# Adafruit_SCD-41.net
KiCad netlist of a schematic drawn in EAGLE
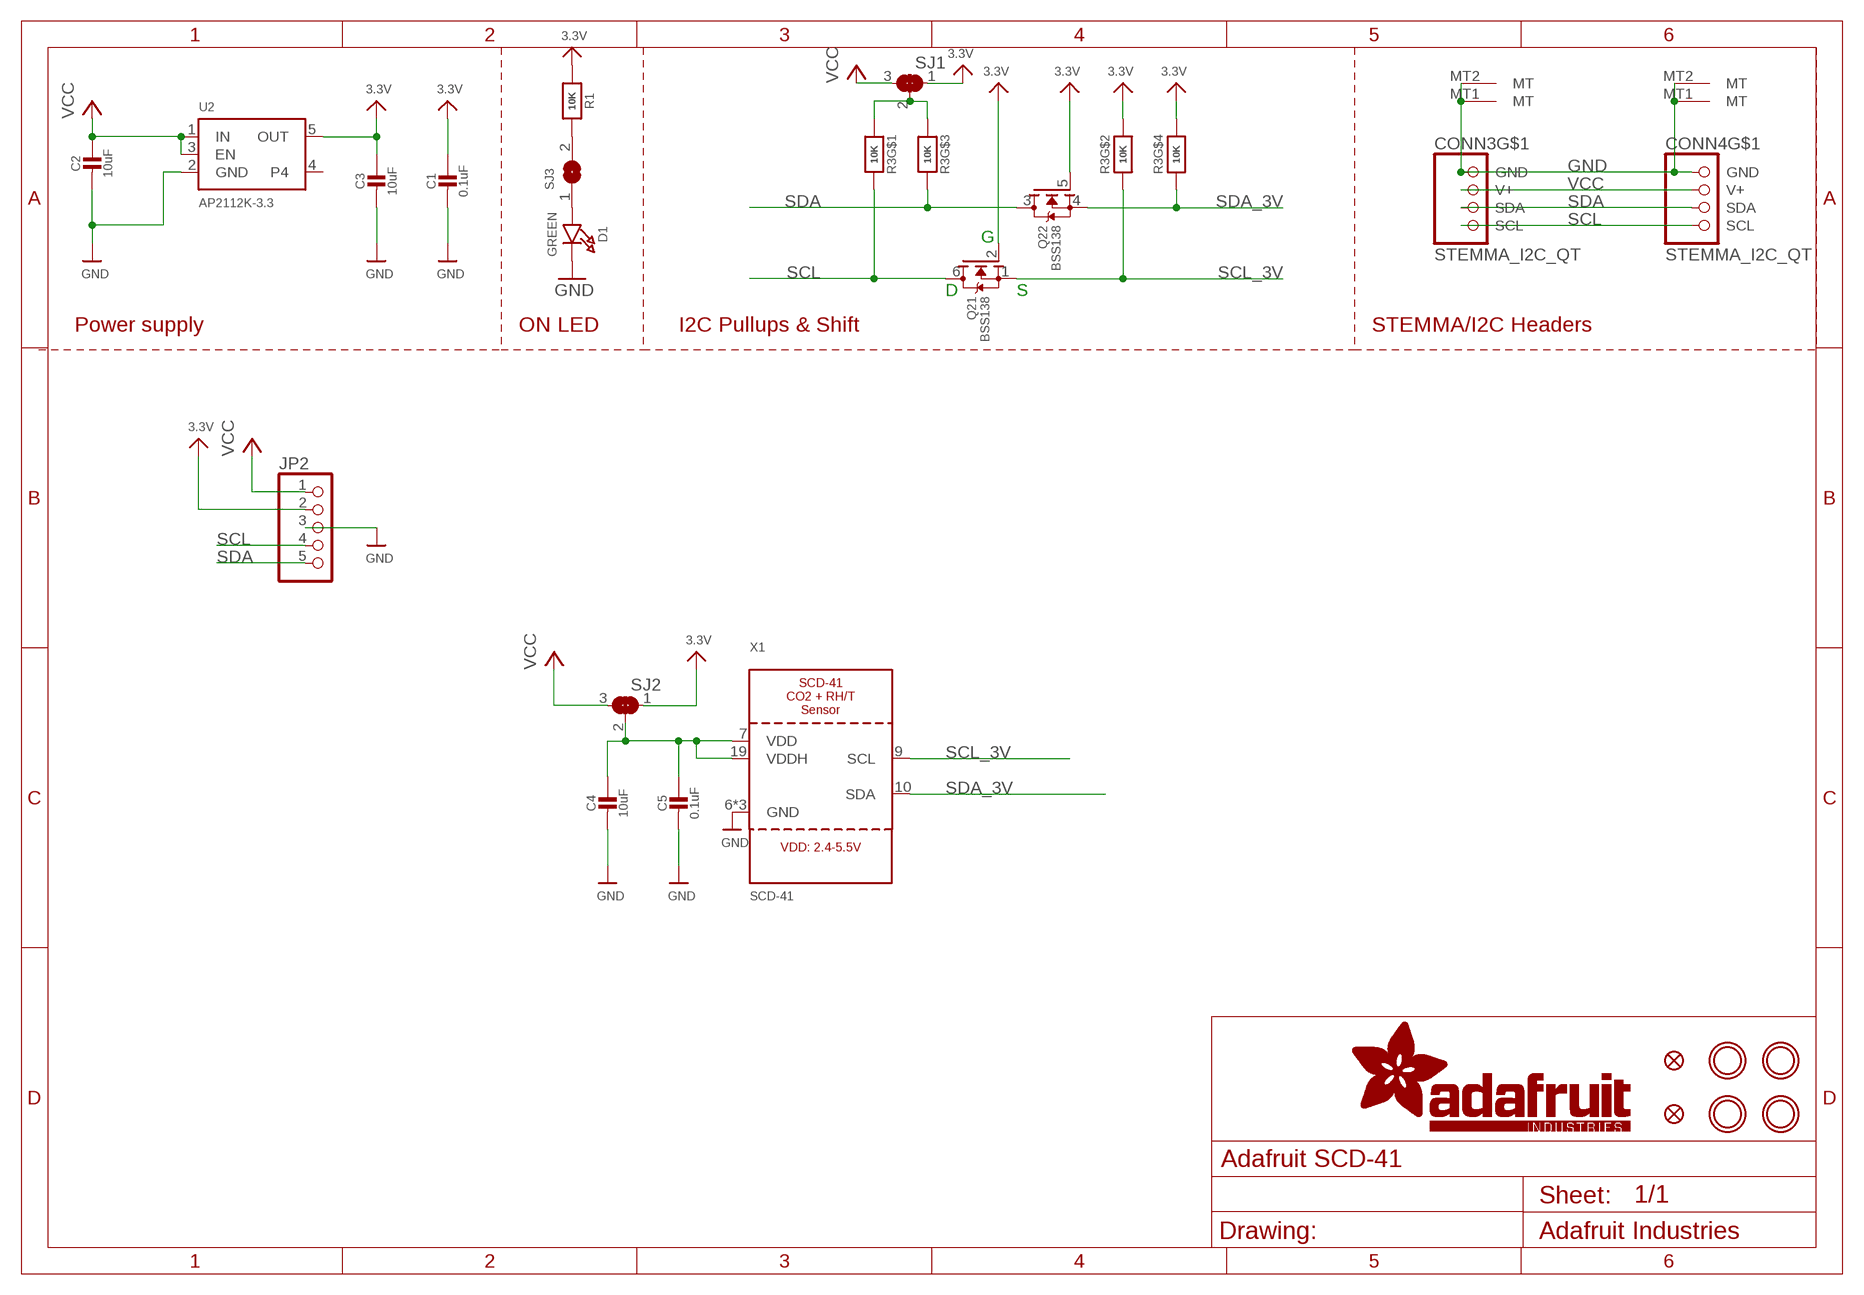
[diagram p0: schematic, sheet 1]

(export (version "E")
  (design (tool "Eeschema 10.0.6"))
  (components
    (comp (ref "C1")
      (value "0.1uF")
      (footprint "eagle-import:0603-NO")
      (libsource (lib "eagle-import") (part "CAP_CERAMIC0603_NO"))
    )
    (comp (ref "C2")
      (value "10uF")
      (footprint "eagle-import:0805-NO")
      (libsource (lib "eagle-import") (part "CAP_CERAMIC0805-NOOUTLINE"))
    )
    (comp (ref "C3")
      (value "10uF")
      (footprint "eagle-import:0805-NO")
      (libsource (lib "eagle-import") (part "CAP_CERAMIC0805-NOOUTLINE"))
    )
    (comp (ref "C4")
      (value "10uF")
      (footprint "eagle-import:0805-NO")
      (libsource (lib "eagle-import") (part "CAP_CERAMIC0805-NOOUTLINE"))
    )
    (comp (ref "C5")
      (value "0.1uF")
      (footprint "eagle-import:0603-NO")
      (libsource (lib "eagle-import") (part "CAP_CERAMIC0603_NO"))
    )
    (comp (ref "CONN3")
      (value "STEMMA_I2C_QT")
      (footprint "eagle-import:JST_SH4")
      (libsource (lib "eagle-import") (part "STEMMA_I2C_QT"))
    )
    (comp (ref "CONN4")
      (value "STEMMA_I2C_QT")
      (footprint "eagle-import:JST_SH4")
      (libsource (lib "eagle-import") (part "STEMMA_I2C_QT"))
    )
    (comp (ref "D1")
      (value "GREEN")
      (footprint "eagle-import:CHIPLED_0603_NOOUTLINE")
      (libsource (lib "eagle-import") (part "LED0603_NOOUTLINE"))
    )
    (comp (ref "FID3")
      (value "FIDUCIAL_1MM")
      (footprint "eagle-import:FIDUCIAL_1MM")
      (libsource (lib "eagle-import") (part "FIDUCIAL_1MM"))
    )
    (comp (ref "FID4")
      (value "FIDUCIAL_1MM")
      (footprint "eagle-import:FIDUCIAL_1MM")
      (libsource (lib "eagle-import") (part "FIDUCIAL_1MM"))
    )
    (comp (ref "JP2")
      (value "HEADER-1X576MIL")
      (footprint "eagle-import:1X05_ROUND_76")
      (libsource (lib "eagle-import") (part "HEADER-1X576MIL"))
    )
    (comp (ref "Q2")
      (value "BSS138")
      (footprint "eagle-import:SOT363")
      (libsource (lib "eagle-import") (part "MOSFET-N_DUAL"))
    )
    (comp (ref "R1")
      (value "10K")
      (footprint "eagle-import:0603-NO")
      (libsource (lib "eagle-import") (part "RESISTOR_0603_NOOUT"))
    )
    (comp (ref "R3")
      (value "10K")
      (footprint "eagle-import:RESPACK_4X0603")
      (libsource (lib "eagle-import") (part "RESISTOR_4PACK"))
    )
    (comp (ref "SJ1")
      (value "SOLDERJUMPER_2WAY")
      (footprint "eagle-import:SOLDERJUMPER_2WAY_OPEN_NOPASTE")
      (libsource (lib "eagle-import") (part "SOLDERJUMPER_2WAY"))
    )
    (comp (ref "SJ2")
      (value "SOLDERJUMPER_2WAY")
      (footprint "eagle-import:SOLDERJUMPER_2WAY_OPEN_NOPASTE")
      (libsource (lib "eagle-import") (part "SOLDERJUMPER_2WAY"))
    )
    (comp (ref "SJ3")
      (value "SOLDERJUMPERCLOSED")
      (footprint "eagle-import:SOLDERJUMPER_CLOSEDWIRE")
      (libsource (lib "eagle-import") (part "SOLDERJUMPERCLOSED"))
    )
    (comp (ref "U$1")
      (value "MOUNTINGHOLE3.0THIN")
      (footprint "eagle-import:MOUNTINGHOLE_3.0_PLATEDTHIN")
      (libsource (lib "eagle-import") (part "MOUNTINGHOLE3.0THIN"))
    )
    (comp (ref "U$17")
      (value "MOUNTINGHOLE3.0THIN")
      (footprint "eagle-import:MOUNTINGHOLE_3.0_PLATEDTHIN")
      (libsource (lib "eagle-import") (part "MOUNTINGHOLE3.0THIN"))
    )
    (comp (ref "U$19")
      (value "MOUNTINGHOLE3.0THIN")
      (footprint "eagle-import:MOUNTINGHOLE_3.0_PLATEDTHIN")
      (libsource (lib "eagle-import") (part "MOUNTINGHOLE3.0THIN"))
    )
    (comp (ref "U$21")
      (value "MOUNTINGHOLE3.0THIN")
      (footprint "eagle-import:MOUNTINGHOLE_3.0_PLATEDTHIN")
      (libsource (lib "eagle-import") (part "MOUNTINGHOLE3.0THIN"))
    )
    (comp (ref "U2")
      (value "AP2112K-3.3")
      (footprint "eagle-import:SOT23-5")
      (libsource (lib "eagle-import") (part "VREG_SOT23-5"))
    )
    (comp (ref "X1")
      (value "SCD-41")
      (footprint "eagle-import:SCD41")
      (libsource (lib "eagle-import") (part "SCD-41"))
    )
  )
  (nets
    (net (code "1") (name "/SCL") (class "Default")
      (node (ref "CONN3") (pin "4") (pinfunction "SCL_4") (pintype "passive"))
      (node (ref "CONN4") (pin "4") (pinfunction "SCL_4") (pintype "passive"))
      (node (ref "JP2") (pin "4") (pinfunction "4_4") (pintype "passive"))
      (node (ref "Q2") (pin "6") (pinfunction "D_6") (pintype "bidirectional"))
      (node (ref "R3") (pin "8") (pinfunction "2_8") (pintype "passive"))
    )
    (net (code "2") (name "/SCL_3V") (class "Default")
      (node (ref "Q2") (pin "1") (pinfunction "S_1") (pintype "bidirectional"))
      (node (ref "R3") (pin "7") (pinfunction "2_7") (pintype "passive"))
      (node (ref "X1") (pin "9") (pinfunction "SCL_9") (pintype "input"))
    )
    (net (code "3") (name "/SDA") (class "Default")
      (node (ref "CONN3") (pin "3") (pinfunction "SDA_3") (pintype "passive"))
      (node (ref "CONN4") (pin "3") (pinfunction "SDA_3") (pintype "passive"))
      (node (ref "JP2") (pin "5") (pinfunction "5_5") (pintype "passive"))
      (node (ref "Q2") (pin "3") (pinfunction "D_3") (pintype "bidirectional"))
      (node (ref "R3") (pin "6") (pinfunction "2_6") (pintype "passive"))
    )
    (net (code "4") (name "/SDA_3V") (class "Default")
      (node (ref "Q2") (pin "4") (pinfunction "S_4") (pintype "bidirectional"))
      (node (ref "R3") (pin "5") (pinfunction "2_5") (pintype "passive"))
      (node (ref "X1") (pin "10") (pinfunction "SDA_10") (pintype "bidirectional"))
    )
    (net (code "5") (name "3.3V") (class "Default")
      (node (ref "C1") (pin "1") (pinfunction "1_1") (pintype "passive"))
      (node (ref "C3") (pin "1") (pinfunction "1_1") (pintype "passive"))
      (node (ref "JP2") (pin "2") (pinfunction "2_2") (pintype "passive"))
      (node (ref "Q2") (pin "2") (pinfunction "G_2") (pintype "bidirectional"))
      (node (ref "Q2") (pin "5") (pinfunction "G_5") (pintype "bidirectional"))
      (node (ref "R1") (pin "1") (pinfunction "1_1") (pintype "passive"))
      (node (ref "R3") (pin "2") (pinfunction "1_2") (pintype "passive"))
      (node (ref "R3") (pin "4") (pinfunction "1_4") (pintype "passive"))
      (node (ref "SJ1") (pin "1") (pinfunction "1_1") (pintype "passive"))
      (node (ref "SJ2") (pin "1") (pinfunction "1_1") (pintype "passive"))
      (node (ref "U2") (pin "5") (pinfunction "OUT_5") (pintype "power_in"))
    )
    (net (code "6") (name "GND") (class "Default")
      (node (ref "C1") (pin "2") (pinfunction "2_2") (pintype "passive"))
      (node (ref "C2") (pin "2") (pinfunction "2_2") (pintype "passive"))
      (node (ref "C3") (pin "2") (pinfunction "2_2") (pintype "passive"))
      (node (ref "C4") (pin "2") (pinfunction "2_2") (pintype "passive"))
      (node (ref "C5") (pin "2") (pinfunction "2_2") (pintype "passive"))
      (node (ref "CONN3") (pin "1") (pinfunction "GND_1") (pintype "passive"))
      (node (ref "CONN3") (pin "MT1") (pinfunction "MT_MT1") (pintype "bidirectional"))
      (node (ref "CONN3") (pin "MT2") (pinfunction "MT_MT2") (pintype "bidirectional"))
      (node (ref "CONN4") (pin "1") (pinfunction "GND_1") (pintype "passive"))
      (node (ref "CONN4") (pin "MT1") (pinfunction "MT_MT1") (pintype "bidirectional"))
      (node (ref "CONN4") (pin "MT2") (pinfunction "MT_MT2") (pintype "bidirectional"))
      (node (ref "D1") (pin "C") (pinfunction "C_C") (pintype "passive"))
      (node (ref "JP2") (pin "3") (pinfunction "3_3") (pintype "passive"))
      (node (ref "U2") (pin "2") (pinfunction "GND_2") (pintype "power_in"))
      (node (ref "X1") (pin "20") (pinfunction "GND_20") (pintype "power_in"))
      (node (ref "X1") (pin "6") (pinfunction "GND_6") (pintype "power_in"))
      (node (ref "X1") (pin "P$1") (pinfunction "GND_P$1") (pintype "power_in"))
    )
    (net (code "7") (name "Net-(D1-PadA)") (class "Default")
      (node (ref "D1") (pin "A") (pinfunction "A_A") (pintype "passive"))
      (node (ref "SJ3") (pin "1") (pinfunction "1_1") (pintype "passive"))
    )
    (net (code "8") (name "Net-(R1-Pad2)") (class "Default")
      (node (ref "R1") (pin "2") (pinfunction "2_2") (pintype "passive"))
      (node (ref "SJ3") (pin "2") (pinfunction "2_2") (pintype "passive"))
    )
    (net (code "9") (name "Net-(R3C-1)") (class "Default")
      (node (ref "R3") (pin "1") (pinfunction "1_1") (pintype "passive"))
      (node (ref "R3") (pin "3") (pinfunction "1_3") (pintype "passive"))
      (node (ref "SJ1") (pin "2") (pinfunction "2_2") (pintype "passive"))
    )
    (net (code "10") (name "Net-(X1-VDD)") (class "Default")
      (node (ref "C4") (pin "1") (pinfunction "1_1") (pintype "passive"))
      (node (ref "C5") (pin "1") (pinfunction "1_1") (pintype "passive"))
      (node (ref "SJ2") (pin "2") (pinfunction "2_2") (pintype "passive"))
      (node (ref "X1") (pin "19") (pinfunction "VDDH_19") (pintype "power_in"))
      (node (ref "X1") (pin "7") (pinfunction "VDD_7") (pintype "power_in"))
    )
    (net (code "11") (name "VCC") (class "Default")
      (node (ref "C2") (pin "1") (pinfunction "1_1") (pintype "passive"))
      (node (ref "CONN3") (pin "2") (pinfunction "V+_2") (pintype "passive"))
      (node (ref "CONN4") (pin "2") (pinfunction "V+_2") (pintype "passive"))
      (node (ref "JP2") (pin "1") (pinfunction "1_1") (pintype "passive"))
      (node (ref "SJ1") (pin "3") (pinfunction "3_3") (pintype "passive"))
      (node (ref "SJ2") (pin "3") (pinfunction "3_3") (pintype "passive"))
      (node (ref "U2") (pin "1") (pinfunction "IN_1") (pintype "power_in"))
      (node (ref "U2") (pin "3") (pinfunction "EN_3") (pintype "input"))
    )
    (net (code "12") (name "unconnected-(U2-P4-Pad4)") (class "Default")
      (node (ref "U2") (pin "4") (pinfunction "P4_4") (pintype "bidirectional"))
    )
  )
)
